# NeoKey_5x6_Ortho_Snap-Apart.net
KiCad netlist of a schematic drawn in EAGLE
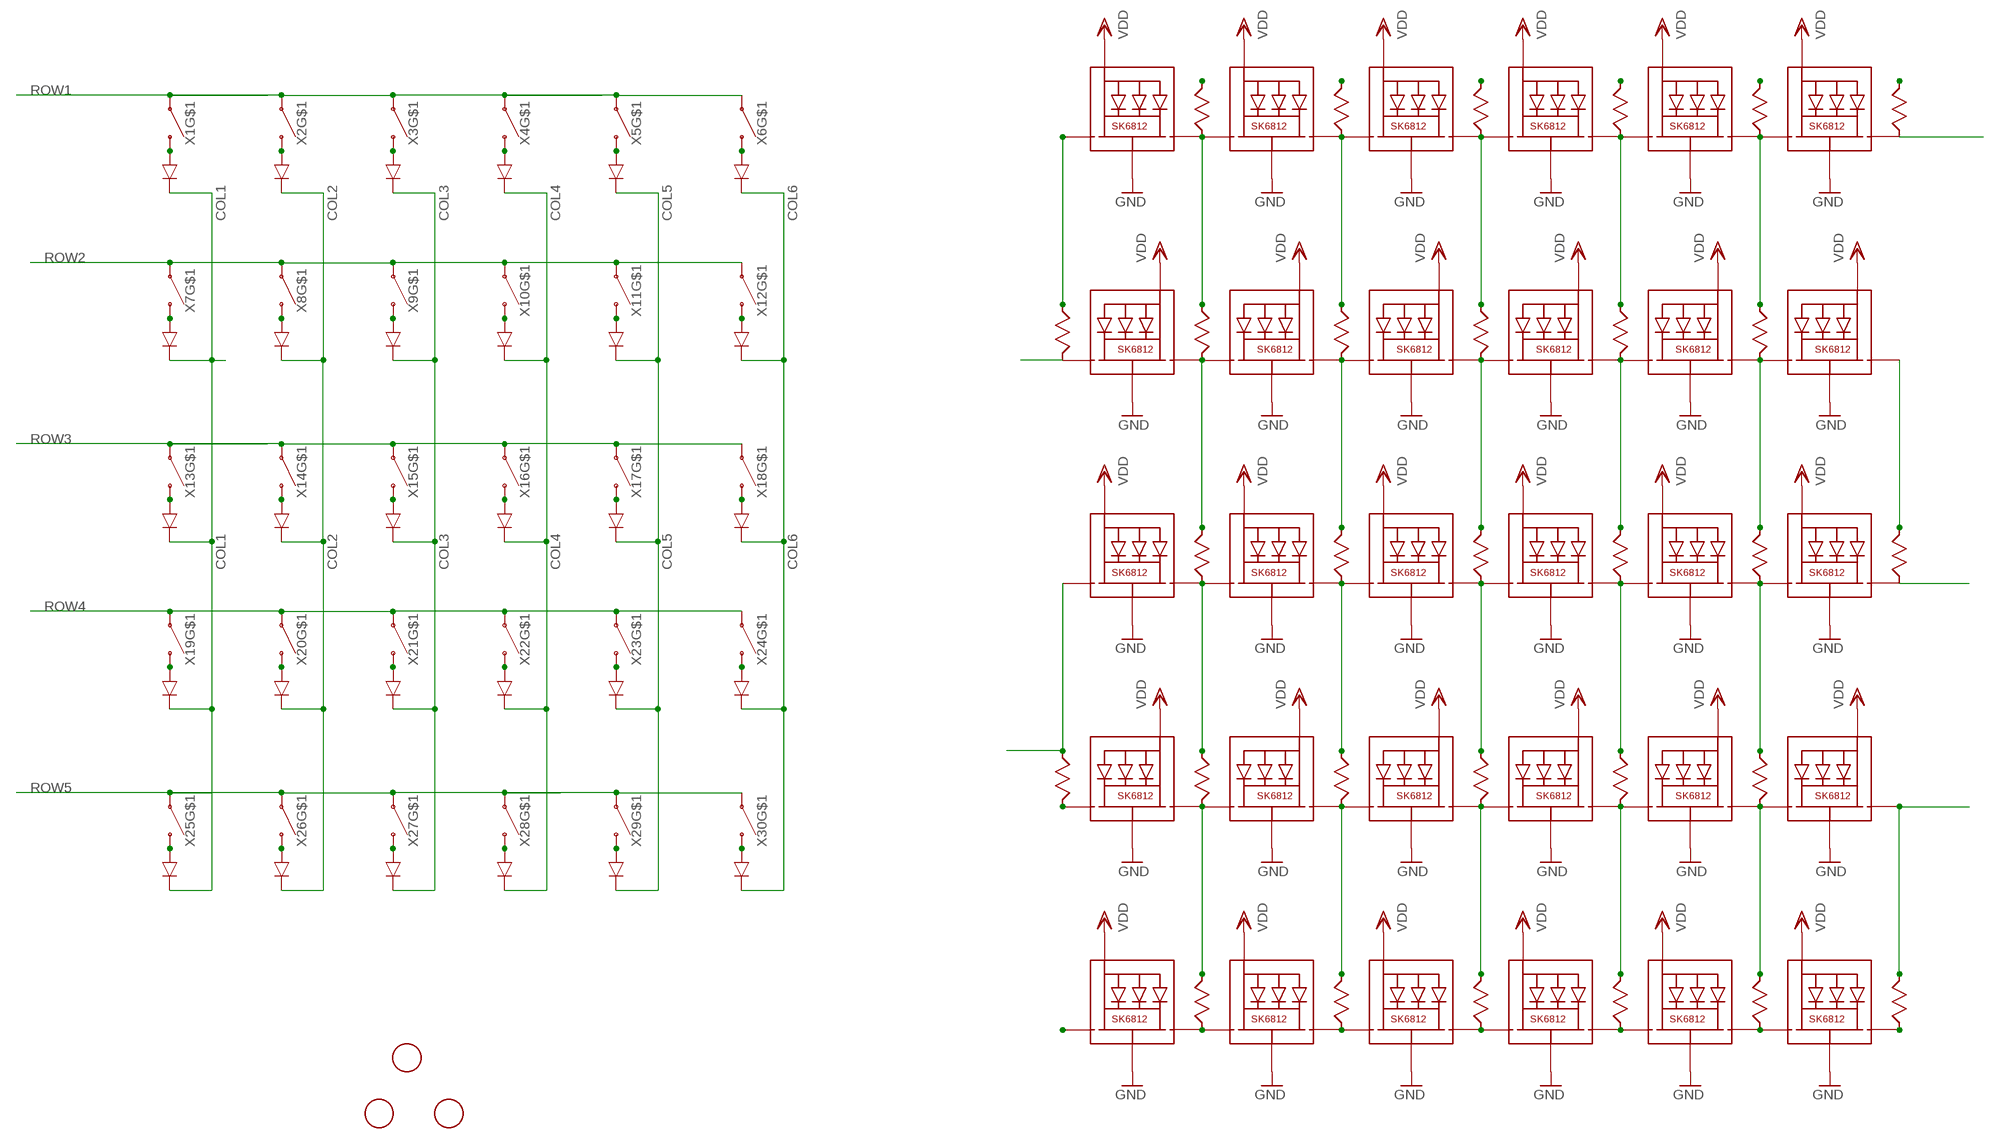
[diagram p0: schematic, sheet 1]

(export (version "E")
  (design (tool "Eeschema 10.0.6"))
  (components
    (comp (ref "U$1")
      (value "FIDUCIAL")
      (footprint "eagle-import:FIDUCIAL_1MM")
      (libsource (lib "eagle-import") (part "FIDUCIAL"))
    )
    (comp (ref "U$2")
      (value "FIDUCIAL")
      (footprint "eagle-import:FIDUCIAL_1MM")
      (libsource (lib "eagle-import") (part "FIDUCIAL"))
    )
    (comp (ref "U$3")
      (value "FIDUCIAL")
      (footprint "eagle-import:FIDUCIAL_1MM")
      (libsource (lib "eagle-import") (part "FIDUCIAL"))
    )
    (comp (ref "X1")
      (value "KAILH_SOCKET_TILE")
      (footprint "eagle-import:KAILH_SOCKET_TILE")
      (libsource (lib "eagle-import") (part "KAILH_SOCKET_TILE"))
    )
    (comp (ref "X2")
      (value "KAILH_SOCKET_TILE")
      (footprint "eagle-import:KAILH_SOCKET_TILE")
      (libsource (lib "eagle-import") (part "KAILH_SOCKET_TILE"))
    )
    (comp (ref "X3")
      (value "KAILH_SOCKET_TILE")
      (footprint "eagle-import:KAILH_SOCKET_TILE")
      (libsource (lib "eagle-import") (part "KAILH_SOCKET_TILE"))
    )
    (comp (ref "X4")
      (value "KAILH_SOCKET_TILE")
      (footprint "eagle-import:KAILH_SOCKET_TILE")
      (libsource (lib "eagle-import") (part "KAILH_SOCKET_TILE"))
    )
    (comp (ref "X5")
      (value "KAILH_SOCKET_TILE")
      (footprint "eagle-import:KAILH_SOCKET_TILE")
      (libsource (lib "eagle-import") (part "KAILH_SOCKET_TILE"))
    )
    (comp (ref "X6")
      (value "KAILH_SOCKET_TILE")
      (footprint "eagle-import:KAILH_SOCKET_TILE")
      (libsource (lib "eagle-import") (part "KAILH_SOCKET_TILE"))
    )
    (comp (ref "X7")
      (value "KAILH_SOCKET_TILE_REVERSE")
      (footprint "eagle-import:KAILH_SOCKET_TILE_REV")
      (libsource (lib "eagle-import") (part "KAILH_SOCKET_TILE_REVERSE"))
    )
    (comp (ref "X8")
      (value "KAILH_SOCKET_TILE_REVERSE")
      (footprint "eagle-import:KAILH_SOCKET_TILE_REV")
      (libsource (lib "eagle-import") (part "KAILH_SOCKET_TILE_REVERSE"))
    )
    (comp (ref "X9")
      (value "KAILH_SOCKET_TILE_REVERSE")
      (footprint "eagle-import:KAILH_SOCKET_TILE_REV")
      (libsource (lib "eagle-import") (part "KAILH_SOCKET_TILE_REVERSE"))
    )
    (comp (ref "X10")
      (value "KAILH_SOCKET_TILE_REVERSE")
      (footprint "eagle-import:KAILH_SOCKET_TILE_REV")
      (libsource (lib "eagle-import") (part "KAILH_SOCKET_TILE_REVERSE"))
    )
    (comp (ref "X11")
      (value "KAILH_SOCKET_TILE_REVERSE")
      (footprint "eagle-import:KAILH_SOCKET_TILE_REV")
      (libsource (lib "eagle-import") (part "KAILH_SOCKET_TILE_REVERSE"))
    )
    (comp (ref "X12")
      (value "KAILH_SOCKET_TILE_REVERSE")
      (footprint "eagle-import:KAILH_SOCKET_TILE_REV")
      (libsource (lib "eagle-import") (part "KAILH_SOCKET_TILE_REVERSE"))
    )
    (comp (ref "X13")
      (value "KAILH_SOCKET_TILE")
      (footprint "eagle-import:KAILH_SOCKET_TILE")
      (libsource (lib "eagle-import") (part "KAILH_SOCKET_TILE"))
    )
    (comp (ref "X14")
      (value "KAILH_SOCKET_TILE")
      (footprint "eagle-import:KAILH_SOCKET_TILE")
      (libsource (lib "eagle-import") (part "KAILH_SOCKET_TILE"))
    )
    (comp (ref "X15")
      (value "KAILH_SOCKET_TILE")
      (footprint "eagle-import:KAILH_SOCKET_TILE")
      (libsource (lib "eagle-import") (part "KAILH_SOCKET_TILE"))
    )
    (comp (ref "X16")
      (value "KAILH_SOCKET_TILE")
      (footprint "eagle-import:KAILH_SOCKET_TILE")
      (libsource (lib "eagle-import") (part "KAILH_SOCKET_TILE"))
    )
    (comp (ref "X17")
      (value "KAILH_SOCKET_TILE")
      (footprint "eagle-import:KAILH_SOCKET_TILE")
      (libsource (lib "eagle-import") (part "KAILH_SOCKET_TILE"))
    )
    (comp (ref "X18")
      (value "KAILH_SOCKET_TILE")
      (footprint "eagle-import:KAILH_SOCKET_TILE")
      (libsource (lib "eagle-import") (part "KAILH_SOCKET_TILE"))
    )
    (comp (ref "X19")
      (value "KAILH_SOCKET_TILE_REVERSE")
      (footprint "eagle-import:KAILH_SOCKET_TILE_REV")
      (libsource (lib "eagle-import") (part "KAILH_SOCKET_TILE_REVERSE"))
    )
    (comp (ref "X20")
      (value "KAILH_SOCKET_TILE_REVERSE")
      (footprint "eagle-import:KAILH_SOCKET_TILE_REV")
      (libsource (lib "eagle-import") (part "KAILH_SOCKET_TILE_REVERSE"))
    )
    (comp (ref "X21")
      (value "KAILH_SOCKET_TILE_REVERSE")
      (footprint "eagle-import:KAILH_SOCKET_TILE_REV")
      (libsource (lib "eagle-import") (part "KAILH_SOCKET_TILE_REVERSE"))
    )
    (comp (ref "X22")
      (value "KAILH_SOCKET_TILE_REVERSE")
      (footprint "eagle-import:KAILH_SOCKET_TILE_REV")
      (libsource (lib "eagle-import") (part "KAILH_SOCKET_TILE_REVERSE"))
    )
    (comp (ref "X23")
      (value "KAILH_SOCKET_TILE_REVERSE")
      (footprint "eagle-import:KAILH_SOCKET_TILE_REV")
      (libsource (lib "eagle-import") (part "KAILH_SOCKET_TILE_REVERSE"))
    )
    (comp (ref "X24")
      (value "KAILH_SOCKET_TILE_REVERSE")
      (footprint "eagle-import:KAILH_SOCKET_TILE_REV")
      (libsource (lib "eagle-import") (part "KAILH_SOCKET_TILE_REVERSE"))
    )
    (comp (ref "X25")
      (value "KAILH_SOCKET_TILE")
      (footprint "eagle-import:KAILH_SOCKET_TILE")
      (libsource (lib "eagle-import") (part "KAILH_SOCKET_TILE"))
    )
    (comp (ref "X26")
      (value "KAILH_SOCKET_TILE")
      (footprint "eagle-import:KAILH_SOCKET_TILE")
      (libsource (lib "eagle-import") (part "KAILH_SOCKET_TILE"))
    )
    (comp (ref "X27")
      (value "KAILH_SOCKET_TILE")
      (footprint "eagle-import:KAILH_SOCKET_TILE")
      (libsource (lib "eagle-import") (part "KAILH_SOCKET_TILE"))
    )
    (comp (ref "X28")
      (value "KAILH_SOCKET_TILE")
      (footprint "eagle-import:KAILH_SOCKET_TILE")
      (libsource (lib "eagle-import") (part "KAILH_SOCKET_TILE"))
    )
    (comp (ref "X29")
      (value "KAILH_SOCKET_TILE")
      (footprint "eagle-import:KAILH_SOCKET_TILE")
      (libsource (lib "eagle-import") (part "KAILH_SOCKET_TILE"))
    )
    (comp (ref "X30")
      (value "KAILH_SOCKET_TILE")
      (footprint "eagle-import:KAILH_SOCKET_TILE")
      (libsource (lib "eagle-import") (part "KAILH_SOCKET_TILE"))
    )
  )
  (nets
    (net (code "1") (name "/COL1") (class "Default")
      (node (ref "X1") (pin "C") (pinfunction "SW_C_C") (pintype "bidirectional"))
      (node (ref "X1") (pin "C1") (pinfunction "SW_C_C1") (pintype "bidirectional"))
      (node (ref "X1") (pin "C2") (pinfunction "SW_C_C2") (pintype "bidirectional"))
      (node (ref "X13") (pin "C") (pinfunction "SW_C_C") (pintype "bidirectional"))
      (node (ref "X13") (pin "C1") (pinfunction "SW_C_C1") (pintype "bidirectional"))
      (node (ref "X13") (pin "C2") (pinfunction "SW_C_C2") (pintype "bidirectional"))
      (node (ref "X19") (pin "C") (pinfunction "SW_C_C") (pintype "bidirectional"))
      (node (ref "X19") (pin "C1") (pinfunction "SW_C_C1") (pintype "bidirectional"))
      (node (ref "X19") (pin "C2") (pinfunction "SW_C_C2") (pintype "bidirectional"))
      (node (ref "X25") (pin "C") (pinfunction "SW_C_C") (pintype "bidirectional"))
      (node (ref "X25") (pin "C1") (pinfunction "SW_C_C1") (pintype "bidirectional"))
      (node (ref "X25") (pin "C2") (pinfunction "SW_C_C2") (pintype "bidirectional"))
      (node (ref "X7") (pin "C") (pinfunction "SW_C_C") (pintype "bidirectional"))
      (node (ref "X7") (pin "C1") (pinfunction "SW_C_C1") (pintype "bidirectional"))
      (node (ref "X7") (pin "C2") (pinfunction "SW_C_C2") (pintype "bidirectional"))
    )
    (net (code "2") (name "/COL2") (class "Default")
      (node (ref "X14") (pin "C") (pinfunction "SW_C_C") (pintype "bidirectional"))
      (node (ref "X14") (pin "C1") (pinfunction "SW_C_C1") (pintype "bidirectional"))
      (node (ref "X14") (pin "C2") (pinfunction "SW_C_C2") (pintype "bidirectional"))
      (node (ref "X2") (pin "C") (pinfunction "SW_C_C") (pintype "bidirectional"))
      (node (ref "X2") (pin "C1") (pinfunction "SW_C_C1") (pintype "bidirectional"))
      (node (ref "X2") (pin "C2") (pinfunction "SW_C_C2") (pintype "bidirectional"))
      (node (ref "X20") (pin "C") (pinfunction "SW_C_C") (pintype "bidirectional"))
      (node (ref "X20") (pin "C1") (pinfunction "SW_C_C1") (pintype "bidirectional"))
      (node (ref "X20") (pin "C2") (pinfunction "SW_C_C2") (pintype "bidirectional"))
      (node (ref "X26") (pin "C") (pinfunction "SW_C_C") (pintype "bidirectional"))
      (node (ref "X26") (pin "C1") (pinfunction "SW_C_C1") (pintype "bidirectional"))
      (node (ref "X26") (pin "C2") (pinfunction "SW_C_C2") (pintype "bidirectional"))
      (node (ref "X8") (pin "C") (pinfunction "SW_C_C") (pintype "bidirectional"))
      (node (ref "X8") (pin "C1") (pinfunction "SW_C_C1") (pintype "bidirectional"))
      (node (ref "X8") (pin "C2") (pinfunction "SW_C_C2") (pintype "bidirectional"))
    )
    (net (code "3") (name "/COL3") (class "Default")
      (node (ref "X15") (pin "C") (pinfunction "SW_C_C") (pintype "bidirectional"))
      (node (ref "X15") (pin "C1") (pinfunction "SW_C_C1") (pintype "bidirectional"))
      (node (ref "X15") (pin "C2") (pinfunction "SW_C_C2") (pintype "bidirectional"))
      (node (ref "X21") (pin "C") (pinfunction "SW_C_C") (pintype "bidirectional"))
      (node (ref "X21") (pin "C1") (pinfunction "SW_C_C1") (pintype "bidirectional"))
      (node (ref "X21") (pin "C2") (pinfunction "SW_C_C2") (pintype "bidirectional"))
      (node (ref "X27") (pin "C") (pinfunction "SW_C_C") (pintype "bidirectional"))
      (node (ref "X27") (pin "C1") (pinfunction "SW_C_C1") (pintype "bidirectional"))
      (node (ref "X27") (pin "C2") (pinfunction "SW_C_C2") (pintype "bidirectional"))
      (node (ref "X3") (pin "C") (pinfunction "SW_C_C") (pintype "bidirectional"))
      (node (ref "X3") (pin "C1") (pinfunction "SW_C_C1") (pintype "bidirectional"))
      (node (ref "X3") (pin "C2") (pinfunction "SW_C_C2") (pintype "bidirectional"))
      (node (ref "X9") (pin "C") (pinfunction "SW_C_C") (pintype "bidirectional"))
      (node (ref "X9") (pin "C1") (pinfunction "SW_C_C1") (pintype "bidirectional"))
      (node (ref "X9") (pin "C2") (pinfunction "SW_C_C2") (pintype "bidirectional"))
    )
    (net (code "4") (name "/COL4") (class "Default")
      (node (ref "X10") (pin "C") (pinfunction "SW_C_C") (pintype "bidirectional"))
      (node (ref "X10") (pin "C1") (pinfunction "SW_C_C1") (pintype "bidirectional"))
      (node (ref "X10") (pin "C2") (pinfunction "SW_C_C2") (pintype "bidirectional"))
      (node (ref "X16") (pin "C") (pinfunction "SW_C_C") (pintype "bidirectional"))
      (node (ref "X16") (pin "C1") (pinfunction "SW_C_C1") (pintype "bidirectional"))
      (node (ref "X16") (pin "C2") (pinfunction "SW_C_C2") (pintype "bidirectional"))
      (node (ref "X22") (pin "C") (pinfunction "SW_C_C") (pintype "bidirectional"))
      (node (ref "X22") (pin "C1") (pinfunction "SW_C_C1") (pintype "bidirectional"))
      (node (ref "X22") (pin "C2") (pinfunction "SW_C_C2") (pintype "bidirectional"))
      (node (ref "X28") (pin "C") (pinfunction "SW_C_C") (pintype "bidirectional"))
      (node (ref "X28") (pin "C1") (pinfunction "SW_C_C1") (pintype "bidirectional"))
      (node (ref "X28") (pin "C2") (pinfunction "SW_C_C2") (pintype "bidirectional"))
      (node (ref "X4") (pin "C") (pinfunction "SW_C_C") (pintype "bidirectional"))
      (node (ref "X4") (pin "C1") (pinfunction "SW_C_C1") (pintype "bidirectional"))
      (node (ref "X4") (pin "C2") (pinfunction "SW_C_C2") (pintype "bidirectional"))
    )
    (net (code "5") (name "/COL5") (class "Default")
      (node (ref "X11") (pin "C") (pinfunction "SW_C_C") (pintype "bidirectional"))
      (node (ref "X11") (pin "C1") (pinfunction "SW_C_C1") (pintype "bidirectional"))
      (node (ref "X11") (pin "C2") (pinfunction "SW_C_C2") (pintype "bidirectional"))
      (node (ref "X17") (pin "C") (pinfunction "SW_C_C") (pintype "bidirectional"))
      (node (ref "X17") (pin "C1") (pinfunction "SW_C_C1") (pintype "bidirectional"))
      (node (ref "X17") (pin "C2") (pinfunction "SW_C_C2") (pintype "bidirectional"))
      (node (ref "X23") (pin "C") (pinfunction "SW_C_C") (pintype "bidirectional"))
      (node (ref "X23") (pin "C1") (pinfunction "SW_C_C1") (pintype "bidirectional"))
      (node (ref "X23") (pin "C2") (pinfunction "SW_C_C2") (pintype "bidirectional"))
      (node (ref "X29") (pin "C") (pinfunction "SW_C_C") (pintype "bidirectional"))
      (node (ref "X29") (pin "C1") (pinfunction "SW_C_C1") (pintype "bidirectional"))
      (node (ref "X29") (pin "C2") (pinfunction "SW_C_C2") (pintype "bidirectional"))
      (node (ref "X5") (pin "C") (pinfunction "SW_C_C") (pintype "bidirectional"))
      (node (ref "X5") (pin "C1") (pinfunction "SW_C_C1") (pintype "bidirectional"))
      (node (ref "X5") (pin "C2") (pinfunction "SW_C_C2") (pintype "bidirectional"))
    )
    (net (code "6") (name "/COL6") (class "Default")
      (node (ref "X12") (pin "C") (pinfunction "SW_C_C") (pintype "bidirectional"))
      (node (ref "X12") (pin "C1") (pinfunction "SW_C_C1") (pintype "bidirectional"))
      (node (ref "X12") (pin "C2") (pinfunction "SW_C_C2") (pintype "bidirectional"))
      (node (ref "X18") (pin "C") (pinfunction "SW_C_C") (pintype "bidirectional"))
      (node (ref "X18") (pin "C1") (pinfunction "SW_C_C1") (pintype "bidirectional"))
      (node (ref "X18") (pin "C2") (pinfunction "SW_C_C2") (pintype "bidirectional"))
      (node (ref "X24") (pin "C") (pinfunction "SW_C_C") (pintype "bidirectional"))
      (node (ref "X24") (pin "C1") (pinfunction "SW_C_C1") (pintype "bidirectional"))
      (node (ref "X24") (pin "C2") (pinfunction "SW_C_C2") (pintype "bidirectional"))
      (node (ref "X30") (pin "C") (pinfunction "SW_C_C") (pintype "bidirectional"))
      (node (ref "X30") (pin "C1") (pinfunction "SW_C_C1") (pintype "bidirectional"))
      (node (ref "X30") (pin "C2") (pinfunction "SW_C_C2") (pintype "bidirectional"))
      (node (ref "X6") (pin "C") (pinfunction "SW_C_C") (pintype "bidirectional"))
      (node (ref "X6") (pin "C1") (pinfunction "SW_C_C1") (pintype "bidirectional"))
      (node (ref "X6") (pin "C2") (pinfunction "SW_C_C2") (pintype "bidirectional"))
    )
    (net (code "7") (name "/ROW1") (class "Default")
      (node (ref "X1") (pin "A") (pinfunction "SW_A_A") (pintype "bidirectional"))
      (node (ref "X1") (pin "A1") (pinfunction "SW_A_A1") (pintype "bidirectional"))
      (node (ref "X1") (pin "A2") (pinfunction "SW_A_A2") (pintype "bidirectional"))
      (node (ref "X2") (pin "A") (pinfunction "SW_A_A") (pintype "bidirectional"))
      (node (ref "X2") (pin "A1") (pinfunction "SW_A_A1") (pintype "bidirectional"))
      (node (ref "X2") (pin "A2") (pinfunction "SW_A_A2") (pintype "bidirectional"))
      (node (ref "X3") (pin "A") (pinfunction "SW_A_A") (pintype "bidirectional"))
      (node (ref "X3") (pin "A1") (pinfunction "SW_A_A1") (pintype "bidirectional"))
      (node (ref "X3") (pin "A2") (pinfunction "SW_A_A2") (pintype "bidirectional"))
      (node (ref "X4") (pin "A") (pinfunction "SW_A_A") (pintype "bidirectional"))
      (node (ref "X4") (pin "A1") (pinfunction "SW_A_A1") (pintype "bidirectional"))
      (node (ref "X4") (pin "A2") (pinfunction "SW_A_A2") (pintype "bidirectional"))
      (node (ref "X5") (pin "A") (pinfunction "SW_A_A") (pintype "bidirectional"))
      (node (ref "X5") (pin "A1") (pinfunction "SW_A_A1") (pintype "bidirectional"))
      (node (ref "X5") (pin "A2") (pinfunction "SW_A_A2") (pintype "bidirectional"))
      (node (ref "X6") (pin "A") (pinfunction "SW_A_A") (pintype "bidirectional"))
      (node (ref "X6") (pin "A1") (pinfunction "SW_A_A1") (pintype "bidirectional"))
      (node (ref "X6") (pin "A2") (pinfunction "SW_A_A2") (pintype "bidirectional"))
    )
    (net (code "8") (name "/ROW2") (class "Default")
      (node (ref "X10") (pin "A") (pinfunction "SW_A_A") (pintype "bidirectional"))
      (node (ref "X10") (pin "A1") (pinfunction "SW_A_A1") (pintype "bidirectional"))
      (node (ref "X10") (pin "A2") (pinfunction "SW_A_A2") (pintype "bidirectional"))
      (node (ref "X11") (pin "A") (pinfunction "SW_A_A") (pintype "bidirectional"))
      (node (ref "X11") (pin "A1") (pinfunction "SW_A_A1") (pintype "bidirectional"))
      (node (ref "X11") (pin "A2") (pinfunction "SW_A_A2") (pintype "bidirectional"))
      (node (ref "X12") (pin "A") (pinfunction "SW_A_A") (pintype "bidirectional"))
      (node (ref "X12") (pin "A1") (pinfunction "SW_A_A1") (pintype "bidirectional"))
      (node (ref "X12") (pin "A2") (pinfunction "SW_A_A2") (pintype "bidirectional"))
      (node (ref "X7") (pin "A") (pinfunction "SW_A_A") (pintype "bidirectional"))
      (node (ref "X7") (pin "A1") (pinfunction "SW_A_A1") (pintype "bidirectional"))
      (node (ref "X7") (pin "A2") (pinfunction "SW_A_A2") (pintype "bidirectional"))
      (node (ref "X8") (pin "A") (pinfunction "SW_A_A") (pintype "bidirectional"))
      (node (ref "X8") (pin "A1") (pinfunction "SW_A_A1") (pintype "bidirectional"))
      (node (ref "X8") (pin "A2") (pinfunction "SW_A_A2") (pintype "bidirectional"))
      (node (ref "X9") (pin "A") (pinfunction "SW_A_A") (pintype "bidirectional"))
      (node (ref "X9") (pin "A1") (pinfunction "SW_A_A1") (pintype "bidirectional"))
      (node (ref "X9") (pin "A2") (pinfunction "SW_A_A2") (pintype "bidirectional"))
    )
    (net (code "9") (name "/ROW3") (class "Default")
      (node (ref "X13") (pin "A") (pinfunction "SW_A_A") (pintype "bidirectional"))
      (node (ref "X13") (pin "A1") (pinfunction "SW_A_A1") (pintype "bidirectional"))
      (node (ref "X13") (pin "A2") (pinfunction "SW_A_A2") (pintype "bidirectional"))
      (node (ref "X14") (pin "A") (pinfunction "SW_A_A") (pintype "bidirectional"))
      (node (ref "X14") (pin "A1") (pinfunction "SW_A_A1") (pintype "bidirectional"))
      (node (ref "X14") (pin "A2") (pinfunction "SW_A_A2") (pintype "bidirectional"))
      (node (ref "X15") (pin "A") (pinfunction "SW_A_A") (pintype "bidirectional"))
      (node (ref "X15") (pin "A1") (pinfunction "SW_A_A1") (pintype "bidirectional"))
      (node (ref "X15") (pin "A2") (pinfunction "SW_A_A2") (pintype "bidirectional"))
      (node (ref "X16") (pin "A") (pinfunction "SW_A_A") (pintype "bidirectional"))
      (node (ref "X16") (pin "A1") (pinfunction "SW_A_A1") (pintype "bidirectional"))
      (node (ref "X16") (pin "A2") (pinfunction "SW_A_A2") (pintype "bidirectional"))
      (node (ref "X17") (pin "A") (pinfunction "SW_A_A") (pintype "bidirectional"))
      (node (ref "X17") (pin "A1") (pinfunction "SW_A_A1") (pintype "bidirectional"))
      (node (ref "X17") (pin "A2") (pinfunction "SW_A_A2") (pintype "bidirectional"))
      (node (ref "X18") (pin "A") (pinfunction "SW_A_A") (pintype "bidirectional"))
      (node (ref "X18") (pin "A1") (pinfunction "SW_A_A1") (pintype "bidirectional"))
      (node (ref "X18") (pin "A2") (pinfunction "SW_A_A2") (pintype "bidirectional"))
    )
    (net (code "10") (name "/ROW4") (class "Default")
      (node (ref "X19") (pin "A") (pinfunction "SW_A_A") (pintype "bidirectional"))
      (node (ref "X19") (pin "A1") (pinfunction "SW_A_A1") (pintype "bidirectional"))
      (node (ref "X19") (pin "A2") (pinfunction "SW_A_A2") (pintype "bidirectional"))
      (node (ref "X20") (pin "A") (pinfunction "SW_A_A") (pintype "bidirectional"))
      (node (ref "X20") (pin "A1") (pinfunction "SW_A_A1") (pintype "bidirectional"))
      (node (ref "X20") (pin "A2") (pinfunction "SW_A_A2") (pintype "bidirectional"))
      (node (ref "X21") (pin "A") (pinfunction "SW_A_A") (pintype "bidirectional"))
      (node (ref "X21") (pin "A1") (pinfunction "SW_A_A1") (pintype "bidirectional"))
      (node (ref "X21") (pin "A2") (pinfunction "SW_A_A2") (pintype "bidirectional"))
      (node (ref "X22") (pin "A") (pinfunction "SW_A_A") (pintype "bidirectional"))
      (node (ref "X22") (pin "A1") (pinfunction "SW_A_A1") (pintype "bidirectional"))
      (node (ref "X22") (pin "A2") (pinfunction "SW_A_A2") (pintype "bidirectional"))
      (node (ref "X23") (pin "A") (pinfunction "SW_A_A") (pintype "bidirectional"))
      (node (ref "X23") (pin "A1") (pinfunction "SW_A_A1") (pintype "bidirectional"))
      (node (ref "X23") (pin "A2") (pinfunction "SW_A_A2") (pintype "bidirectional"))
      (node (ref "X24") (pin "A") (pinfunction "SW_A_A") (pintype "bidirectional"))
      (node (ref "X24") (pin "A1") (pinfunction "SW_A_A1") (pintype "bidirectional"))
      (node (ref "X24") (pin "A2") (pinfunction "SW_A_A2") (pintype "bidirectional"))
    )
    (net (code "11") (name "/ROW5") (class "Default")
      (node (ref "X25") (pin "A") (pinfunction "SW_A_A") (pintype "bidirectional"))
      (node (ref "X25") (pin "A1") (pinfunction "SW_A_A1") (pintype "bidirectional"))
      (node (ref "X25") (pin "A2") (pinfunction "SW_A_A2") (pintype "bidirectional"))
      (node (ref "X26") (pin "A") (pinfunction "SW_A_A") (pintype "bidirectional"))
      (node (ref "X26") (pin "A1") (pinfunction "SW_A_A1") (pintype "bidirectional"))
      (node (ref "X26") (pin "A2") (pinfunction "SW_A_A2") (pintype "bidirectional"))
      (node (ref "X27") (pin "A") (pinfunction "SW_A_A") (pintype "bidirectional"))
      (node (ref "X27") (pin "A1") (pinfunction "SW_A_A1") (pintype "bidirectional"))
      (node (ref "X27") (pin "A2") (pinfunction "SW_A_A2") (pintype "bidirectional"))
      (node (ref "X28") (pin "A") (pinfunction "SW_A_A") (pintype "bidirectional"))
      (node (ref "X28") (pin "A1") (pinfunction "SW_A_A1") (pintype "bidirectional"))
      (node (ref "X28") (pin "A2") (pinfunction "SW_A_A2") (pintype "bidirectional"))
      (node (ref "X29") (pin "A") (pinfunction "SW_A_A") (pintype "bidirectional"))
      (node (ref "X29") (pin "A1") (pinfunction "SW_A_A1") (pintype "bidirectional"))
      (node (ref "X29") (pin "A2") (pinfunction "SW_A_A2") (pintype "bidirectional"))
      (node (ref "X30") (pin "A") (pinfunction "SW_A_A") (pintype "bidirectional"))
      (node (ref "X30") (pin "A1") (pinfunction "SW_A_A1") (pintype "bidirectional"))
      (node (ref "X30") (pin "A2") (pinfunction "SW_A_A2") (pintype "bidirectional"))
    )
    (net (code "12") (name "GND") (class "Default")
      (node (ref "X1") (pin "3-GND") (pinfunction "GND_3-GND") (pintype "power_in"))
      (node (ref "X1") (pin "C-") (pinfunction "GND_C-") (pintype "power_in"))
      (node (ref "X1") (pin "GND1") (pinfunction "GND_GND1") (pintype "power_in"))
      (node (ref "X1") (pin "GND2") (pinfunction "GND_GND2") (pintype "power_in"))
      (node (ref "X10") (pin "3-GND") (pinfunction "GND_3-GND") (pintype "power_in"))
      (node (ref "X10") (pin "C-") (pinfunction "GND_C-") (pintype "power_in"))
      (node (ref "X10") (pin "GND1") (pinfunction "GND_GND1") (pintype "power_in"))
      (node (ref "X10") (pin "GND2") (pinfunction "GND_GND2") (pintype "power_in"))
      (node (ref "X11") (pin "3-GND") (pinfunction "GND_3-GND") (pintype "power_in"))
      (node (ref "X11") (pin "C-") (pinfunction "GND_C-") (pintype "power_in"))
      (node (ref "X11") (pin "GND1") (pinfunction "GND_GND1") (pintype "power_in"))
      (node (ref "X11") (pin "GND2") (pinfunction "GND_GND2") (pintype "power_in"))
      (node (ref "X12") (pin "3-GND") (pinfunction "GND_3-GND") (pintype "power_in"))
      (node (ref "X12") (pin "C-") (pinfunction "GND_C-") (pintype "power_in"))
      (node (ref "X12") (pin "GND1") (pinfunction "GND_GND1") (pintype "power_in"))
      (node (ref "X12") (pin "GND2") (pinfunction "GND_GND2") (pintype "power_in"))
      (node (ref "X13") (pin "3-GND") (pinfunction "GND_3-GND") (pintype "power_in"))
      (node (ref "X13") (pin "C-") (pinfunction "GND_C-") (pintype "power_in"))
      (node (ref "X13") (pin "GND1") (pinfunction "GND_GND1") (pintype "power_in"))
      (node (ref "X13") (pin "GND2") (pinfunction "GND_GND2") (pintype "power_in"))
      (node (ref "X14") (pin "3-GND") (pinfunction "GND_3-GND") (pintype "power_in"))
      (node (ref "X14") (pin "C-") (pinfunction "GND_C-") (pintype "power_in"))
      (node (ref "X14") (pin "GND1") (pinfunction "GND_GND1") (pintype "power_in"))
      (node (ref "X14") (pin "GND2") (pinfunction "GND_GND2") (pintype "power_in"))
      (node (ref "X15") (pin "3-GND") (pinfunction "GND_3-GND") (pintype "power_in"))
      (node (ref "X15") (pin "C-") (pinfunction "GND_C-") (pintype "power_in"))
      (node (ref "X15") (pin "GND1") (pinfunction "GND_GND1") (pintype "power_in"))
      (node (ref "X15") (pin "GND2") (pinfunction "GND_GND2") (pintype "power_in"))
      (node (ref "X16") (pin "3-GND") (pinfunction "GND_3-GND") (pintype "power_in"))
      (node (ref "X16") (pin "C-") (pinfunction "GND_C-") (pintype "power_in"))
      (node (ref "X16") (pin "GND1") (pinfunction "GND_GND1") (pintype "power_in"))
      (node (ref "X16") (pin "GND2") (pinfunction "GND_GND2") (pintype "power_in"))
      (node (ref "X17") (pin "3-GND") (pinfunction "GND_3-GND") (pintype "power_in"))
      (node (ref "X17") (pin "C-") (pinfunction "GND_C-") (pintype "power_in"))
      (node (ref "X17") (pin "GND1") (pinfunction "GND_GND1") (pintype "power_in"))
      (node (ref "X17") (pin "GND2") (pinfunction "GND_GND2") (pintype "power_in"))
      (node (ref "X18") (pin "3-GND") (pinfunction "GND_3-GND") (pintype "power_in"))
      (node (ref "X18") (pin "C-") (pinfunction "GND_C-") (pintype "power_in"))
      (node (ref "X18") (pin "GND1") (pinfunction "GND_GND1") (pintype "power_in"))
      (node (ref "X18") (pin "GND2") (pinfunction "GND_GND2") (pintype "power_in"))
      (node (ref "X19") (pin "3-GND") (pinfunction "GND_3-GND") (pintype "power_in"))
      (node (ref "X19") (pin "C-") (pinfunction "GND_C-") (pintype "power_in"))
      (node (ref "X19") (pin "GND1") (pinfunction "GND_GND1") (pintype "power_in"))
      (node (ref "X19") (pin "GND2") (pinfunction "GND_GND2") (pintype "power_in"))
      (node (ref "X2") (pin "3-GND") (pinfunction "GND_3-GND") (pintype "power_in"))
      (node (ref "X2") (pin "C-") (pinfunction "GND_C-") (pintype "power_in"))
      (node (ref "X2") (pin "GND1") (pinfunction "GND_GND1") (pintype "power_in"))
      (node (ref "X2") (pin "GND2") (pinfunction "GND_GND2") (pintype "power_in"))
      (node (ref "X20") (pin "3-GND") (pinfunction "GND_3-GND") (pintype "power_in"))
      (node (ref "X20") (pin "C-") (pinfunction "GND_C-") (pintype "power_in"))
      (node (ref "X20") (pin "GND1") (pinfunction "GND_GND1") (pintype "power_in"))
      (node (ref "X20") (pin "GND2") (pinfunction "GND_GND2") (pintype "power_in"))
      (node (ref "X21") (pin "3-GND") (pinfunction "GND_3-GND") (pintype "power_in"))
      (node (ref "X21") (pin "C-") (pinfunction "GND_C-") (pintype "power_in"))
      (node (ref "X21") (pin "GND1") (pinfunction "GND_GND1") (pintype "power_in"))
      (node (ref "X21") (pin "GND2") (pinfunction "GND_GND2") (pintype "power_in"))
      (node (ref "X22") (pin "3-GND") (pinfunction "GND_3-GND") (pintype "power_in"))
      (node (ref "X22") (pin "C-") (pinfunction "GND_C-") (pintype "power_in"))
      (node (ref "X22") (pin "GND1") (pinfunction "GND_GND1") (pintype "power_in"))
      (node (ref "X22") (pin "GND2") (pinfunction "GND_GND2") (pintype "power_in"))
      (node (ref "X23") (pin "3-GND") (pinfunction "GND_3-GND") (pintype "power_in"))
      (node (ref "X23") (pin "C-") (pinfunction "GND_C-") (pintype "power_in"))
      (node (ref "X23") (pin "GND1") (pinfunction "GND_GND1") (pintype "power_in"))
      (node (ref "X23") (pin "GND2") (pinfunction "GND_GND2") (pintype "power_in"))
      (node (ref "X24") (pin "3-GND") (pinfunction "GND_3-GND") (pintype "power_in"))
      (node (ref "X24") (pin "C-") (pinfunction "GND_C-") (pintype "power_in"))
      (node (ref "X24") (pin "GND1") (pinfunction "GND_GND1") (pintype "power_in"))
      (node (ref "X24") (pin "GND2") (pinfunction "GND_GND2") (pintype "power_in"))
      (node (ref "X25") (pin "3-GND") (pinfunction "GND_3-GND") (pintype "power_in"))
      (node (ref "X25") (pin "C-") (pinfunction "GND_C-") (pintype "power_in"))
      (node (ref "X25") (pin "GND1") (pinfunction "GND_GND1") (pintype "power_in"))
      (node (ref "X25") (pin "GND2") (pinfunction "GND_GND2") (pintype "power_in"))
      (node (ref "X26") (pin "3-GND") (pinfunction "GND_3-GND") (pintype "power_in"))
      (node (ref "X26") (pin "C-") (pinfunction "GND_C-") (pintype "power_in"))
      (node (ref "X26") (pin "GND1") (pinfunction "GND_GND1") (pintype "power_in"))
      (node (ref "X26") (pin "GND2") (pinfunction "GND_GND2") (pintype "power_in"))
      (node (ref "X27") (pin "3-GND") (pinfunction "GND_3-GND") (pintype "power_in"))
      (node (ref "X27") (pin "C-") (pinfunction "GND_C-") (pintype "power_in"))
      (node (ref "X27") (pin "GND1") (pinfunction "GND_GND1") (pintype "power_in"))
      (node (ref "X27") (pin "GND2") (pinfunction "GND_GND2") (pintype "power_in"))
      (node (ref "X28") (pin "3-GND") (pinfunction "GND_3-GND") (pintype "power_in"))
      (node (ref "X28") (pin "C-") (pinfunction "GND_C-") (pintype "power_in"))
      (node (ref "X28") (pin "GND1") (pinfunction "GND_GND1") (pintype "power_in"))
      (node (ref "X28") (pin "GND2") (pinfunction "GND_GND2") (pintype "power_in"))
      (node (ref "X29") (pin "3-GND") (pinfunction "GND_3-GND") (pintype "power_in"))
      (node (ref "X29") (pin "C-") (pinfunction "GND_C-") (pintype "power_in"))
      (node (ref "X29") (pin "GND1") (pinfunction "GND_GND1") (pintype "power_in"))
      (node (ref "X29") (pin "GND2") (pinfunction "GND_GND2") (pintype "power_in"))
      (node (ref "X3") (pin "3-GND") (pinfunction "GND_3-GND") (pintype "power_in"))
      (node (ref "X3") (pin "C-") (pinfunction "GND_C-") (pintype "power_in"))
      (node (ref "X3") (pin "GND1") (pinfunction "GND_GND1") (pintype "power_in"))
      (node (ref "X3") (pin "GND2") (pinfunction "GND_GND2") (pintype "power_in"))
      (node (ref "X30") (pin "3-GND") (pinfunction "GND_3-GND") (pintype "power_in"))
      (node (ref "X30") (pin "C-") (pinfunction "GND_C-") (pintype "power_in"))
      (node (ref "X30") (pin "GND1") (pinfunction "GND_GND1") (pintype "power_in"))
      (node (ref "X30") (pin "GND2") (pinfunction "GND_GND2") (pintype "power_in"))
      (node (ref "X4") (pin "3-GND") (pinfunction "GND_3-GND") (pintype "power_in"))
      (node (ref "X4") (pin "C-") (pinfunction "GND_C-") (pintype "power_in"))
      (node (ref "X4") (pin "GND1") (pinfunction "GND_GND1") (pintype "power_in"))
      (node (ref "X4") (pin "GND2") (pinfunction "GND_GND2") (pintype "power_in"))
      (node (ref "X5") (pin "3-GND") (pinfunction "GND_3-GND") (pintype "power_in"))
      (node (ref "X5") (pin "C-") (pinfunction "GND_C-") (pintype "power_in"))
      (node (ref "X5") (pin "GND1") (pinfunction "GND_GND1") (pintype "power_in"))
      (node (ref "X5") (pin "GND2") (pinfunction "GND_GND2") (pintype "power_in"))
      (node (ref "X6") (pin "3-GND") (pinfunction "GND_3-GND") (pintype "power_in"))
      (node (ref "X6") (pin "C-") (pinfunction "GND_C-") (pintype "power_in"))
      (node (ref "X6") (pin "GND1") (pinfunction "GND_GND1") (pintype "power_in"))
      (node (ref "X6") (pin "GND2") (pinfunction "GND_GND2") (pintype "power_in"))
      (node (ref "X7") (pin "3-GND") (pinfunction "GND_3-GND") (pintype "power_in"))
      (node (ref "X7") (pin "C-") (pinfunction "GND_C-") (pintype "power_in"))
      (node (ref "X7") (pin "GND1") (pinfunction "GND_GND1") (pintype "power_in"))
      (node (ref "X7") (pin "GND2") (pinfunction "GND_GND2") (pintype "power_in"))
      (node (ref "X8") (pin "3-GND") (pinfunction "GND_3-GND") (pintype "power_in"))
      (node (ref "X8") (pin "C-") (pinfunction "GND_C-") (pintype "power_in"))
      (node (ref "X8") (pin "GND1") (pinfunction "GND_GND1") (pintype "power_in"))
      (node (ref "X8") (pin "GND2") (pinfunction "GND_GND2") (pintype "power_in"))
      (node (ref "X9") (pin "3-GND") (pinfunction "GND_3-GND") (pintype "power_in"))
      (node (ref "X9") (pin "C-") (pinfunction "GND_C-") (pintype "power_in"))
      (node (ref "X9") (pin "GND1") (pinfunction "GND_GND1") (pintype "power_in"))
      (node (ref "X9") (pin "GND2") (pinfunction "GND_GND2") (pintype "power_in"))
    )
    (net (code "13") (name "Net-(X1-PadDA)") (class "Default")
      (node (ref "X1") (pin "D+") (pinfunction "DA_D+") (pintype "bidirectional"))
      (node (ref "X1") (pin "DA") (pinfunction "DA_DA") (pintype "bidirectional"))
    )
    (net (code "14") (name "Net-(X1B-DI-Pad4-DIN)") (class "Default")
      (node (ref "X1") (pin "4-DIN") (pinfunction "DI_4-DIN") (pintype "input"))
      (node (ref "X1") (pin "DIN") (pinfunction "DI_DIN") (pintype "input"))
      (node (ref "X1") (pin "DIN1") (pinfunction "DI_DIN1") (pintype "input"))
      (node (ref "X2") (pin "2-DOUT") (pinfunction "DO_2-DOUT") (pintype "output"))
      (node (ref "X2") (pin "DOUT") (pinfunction "DO_DOUT") (pintype "output"))
      (node (ref "X2") (pin "DOUT1") (pinfunction "DO_DOUT1") (pintype "output"))
      (node (ref "X8") (pin "DIN_C") (pinfunction "DI1_DIN_C") (pintype "input"))
      (node (ref "X8") (pin "DIN_C1") (pinfunction "DI1_DIN_C1") (pintype "input"))
    )
    (net (code "15") (name "Net-(X1B-DI1-PadDIN_C)") (class "Default")
      (node (ref "X1") (pin "DIN_C") (pinfunction "DI1_DIN_C") (pintype "input"))
      (node (ref "X1") (pin "DIN_C1") (pinfunction "DI1_DIN_C1") (pintype "input"))
    )
    (net (code "16") (name "Net-(X1B-DO-Pad2-DOUT)") (class "Default")
      (node (ref "X1") (pin "2-DOUT") (pinfunction "DO_2-DOUT") (pintype "output"))
      (node (ref "X1") (pin "DOUT") (pinfunction "DO_DOUT") (pintype "output"))
      (node (ref "X1") (pin "DOUT1") (pinfunction "DO_DOUT1") (pintype "output"))
      (node (ref "X7") (pin "DIN_C") (pinfunction "DI1_DIN_C") (pintype "input"))
      (node (ref "X7") (pin "DIN_C1") (pinfunction "DI1_DIN_C1") (pintype "input"))
    )
    (net (code "17") (name "Net-(X2-PadDA)") (class "Default")
      (node (ref "X2") (pin "D+") (pinfunction "DA_D+") (pintype "bidirectional"))
      (node (ref "X2") (pin "DA") (pinfunction "DA_DA") (pintype "bidirectional"))
    )
    (net (code "18") (name "Net-(X2B-DI-Pad4-DIN)") (class "Default")
      (node (ref "X2") (pin "4-DIN") (pinfunction "DI_4-DIN") (pintype "input"))
      (node (ref "X2") (pin "DIN") (pinfunction "DI_DIN") (pintype "input"))
      (node (ref "X2") (pin "DIN1") (pinfunction "DI_DIN1") (pintype "input"))
      (node (ref "X3") (pin "2-DOUT") (pinfunction "DO_2-DOUT") (pintype "output"))
      (node (ref "X3") (pin "DOUT") (pinfunction "DO_DOUT") (pintype "output"))
      (node (ref "X3") (pin "DOUT1") (pinfunction "DO_DOUT1") (pintype "output"))
      (node (ref "X9") (pin "DIN_C") (pinfunction "DI1_DIN_C") (pintype "input"))
      (node (ref "X9") (pin "DIN_C1") (pinfunction "DI1_DIN_C1") (pintype "input"))
    )
    (net (code "19") (name "Net-(X2B-DI1-PadDIN_C)") (class "Default")
      (node (ref "X2") (pin "DIN_C") (pinfunction "DI1_DIN_C") (pintype "input"))
      (node (ref "X2") (pin "DIN_C1") (pinfunction "DI1_DIN_C1") (pintype "input"))
    )
    (net (code "20") (name "Net-(X3-PadDA)") (class "Default")
      (node (ref "X3") (pin "D+") (pinfunction "DA_D+") (pintype "bidirectional"))
      (node (ref "X3") (pin "DA") (pinfunction "DA_DA") (pintype "bidirectional"))
    )
    (net (code "21") (name "Net-(X3B-DI1-PadDIN_C)") (class "Default")
      (node (ref "X3") (pin "DIN_C") (pinfunction "DI1_DIN_C") (pintype "input"))
      (node (ref "X3") (pin "DIN_C1") (pinfunction "DI1_DIN_C1") (pintype "input"))
    )
    (net (code "22") (name "Net-(X4-PadDA)") (class "Default")
      (node (ref "X4") (pin "D+") (pinfunction "DA_D+") (pintype "bidirectional"))
      (node (ref "X4") (pin "DA") (pinfunction "DA_DA") (pintype "bidirectional"))
    )
    (net (code "23") (name "Net-(X4B-DI1-PadDIN_C)") (class "Default")
      (node (ref "X4") (pin "DIN_C") (pinfunction "DI1_DIN_C") (pintype "input"))
      (node (ref "X4") (pin "DIN_C1") (pinfunction "DI1_DIN_C1") (pintype "input"))
    )
    (net (code "24") (name "Net-(X5-PadDA)") (class "Default")
      (node (ref "X5") (pin "D+") (pinfunction "DA_D+") (pintype "bidirectional"))
      (node (ref "X5") (pin "DA") (pinfunction "DA_DA") (pintype "bidirectional"))
    )
    (net (code "25") (name "Net-(X5B-DI1-PadDIN_C)") (class "Default")
      (node (ref "X5") (pin "DIN_C") (pinfunction "DI1_DIN_C") (pintype "input"))
      (node (ref "X5") (pin "DIN_C1") (pinfunction "DI1_DIN_C1") (pintype "input"))
    )
    (net (code "26") (name "Net-(X6-PadDA)") (class "Default")
      (node (ref "X6") (pin "D+") (pinfunction "DA_D+") (pintype "bidirectional"))
      (node (ref "X6") (pin "DA") (pinfunction "DA_DA") (pintype "bidirectional"))
    )
    (net (code "27") (name "Net-(X6B-DI-Pad4-DIN)") (class "Default")
      (node (ref "X6") (pin "4-DIN") (pinfunction "DI_4-DIN") (pintype "input"))
      (node (ref "X6") (pin "DIN") (pinfunction "DI_DIN") (pintype "input"))
      (node (ref "X6") (pin "DIN1") (pinfunction "DI_DIN1") (pintype "input"))
    )
    (net (code "28") (name "Net-(X6B-DI1-PadDIN_C)") (class "Default")
      (node (ref "X6") (pin "DIN_C") (pinfunction "DI1_DIN_C") (pintype "input"))
      (node (ref "X6") (pin "DIN_C1") (pinfunction "DI1_DIN_C1") (pintype "input"))
    )
    (net (code "29") (name "Net-(X7-PadDA)") (class "Default")
      (node (ref "X7") (pin "D+") (pinfunction "DA_D+") (pintype "bidirectional"))
      (node (ref "X7") (pin "DA") (pinfunction "DA_DA") (pintype "bidirectional"))
    )
    (net (code "30") (name "Net-(X7B-DI-Pad4-DIN)") (class "Default")
      (node (ref "X7") (pin "4-DIN") (pinfunction "DI_4-DIN") (pintype "input"))
      (node (ref "X7") (pin "DIN") (pinfunction "DI_DIN") (pintype "input"))
      (node (ref "X7") (pin "DIN1") (pinfunction "DI_DIN1") (pintype "input"))
    )
    (net (code "31") (name "Net-(X8-PadDA)") (class "Default")
      (node (ref "X8") (pin "D+") (pinfunction "DA_D+") (pintype "bidirectional"))
      (node (ref "X8") (pin "DA") (pinfunction "DA_DA") (pintype "bidirectional"))
    )
    (net (code "32") (name "Net-(X9-PadDA)") (class "Default")
      (node (ref "X9") (pin "D+") (pinfunction "DA_D+") (pintype "bidirectional"))
      (node (ref "X9") (pin "DA") (pinfunction "DA_DA") (pintype "bidirectional"))
    )
    (net (code "33") (name "Net-(X10-PadDA)") (class "Default")
      (node (ref "X10") (pin "D+") (pinfunction "DA_D+") (pintype "bidirectional"))
      (node (ref "X10") (pin "DA") (pinfunction "DA_DA") (pintype "bidirectional"))
    )
    (net (code "34") (name "Net-(X10B-DI-Pad4-DIN)") (class "Default")
      (node (ref "X10") (pin "4-DIN") (pinfunction "DI_4-DIN") (pintype "input"))
      (node (ref "X10") (pin "DIN") (pinfunction "DI_DIN") (pintype "input"))
      (node (ref "X10") (pin "DIN1") (pinfunction "DI_DIN1") (pintype "input"))
      (node (ref "X15") (pin "DIN_C") (pinfunction "DI1_DIN_C") (pintype "input"))
      (node (ref "X15") (pin "DIN_C1") (pinfunction "DI1_DIN_C1") (pintype "input"))
      (node (ref "X9") (pin "2-DOUT") (pinfunction "DO_2-DOUT") (pintype "output"))
      (node (ref "X9") (pin "DOUT") (pinfunction "DO_DOUT") (pintype "output"))
      (node (ref "X9") (pin "DOUT1") (pinfunction "DO_DOUT1") (pintype "output"))
    )
    (net (code "35") (name "Net-(X10B-DI1-PadDIN_C)") (class "Default")
      (node (ref "X10") (pin "DIN_C") (pinfunction "DI1_DIN_C") (pintype "input"))
      (node (ref "X10") (pin "DIN_C1") (pinfunction "DI1_DIN_C1") (pintype "input"))
      (node (ref "X3") (pin "4-DIN") (pinfunction "DI_4-DIN") (pintype "input"))
      (node (ref "X3") (pin "DIN") (pinfunction "DI_DIN") (pintype "input"))
      (node (ref "X3") (pin "DIN1") (pinfunction "DI_DIN1") (pintype "input"))
      (node (ref "X4") (pin "2-DOUT") (pinfunction "DO_2-DOUT") (pintype "output"))
      (node (ref "X4") (pin "DOUT") (pinfunction "DO_DOUT") (pintype "output"))
      (node (ref "X4") (pin "DOUT1") (pinfunction "DO_DOUT1") (pintype "output"))
    )
    (net (code "36") (name "Net-(X10B-DO-Pad2-DOUT)") (class "Default")
      (node (ref "X10") (pin "2-DOUT") (pinfunction "DO_2-DOUT") (pintype "output"))
      (node (ref "X10") (pin "DOUT") (pinfunction "DO_DOUT") (pintype "output"))
      (node (ref "X10") (pin "DOUT1") (pinfunction "DO_DOUT1") (pintype "output"))
      (node (ref "X11") (pin "4-DIN") (pinfunction "DI_4-DIN") (pintype "input"))
      (node (ref "X11") (pin "DIN") (pinfunction "DI_DIN") (pintype "input"))
      (node (ref "X11") (pin "DIN1") (pinfunction "DI_DIN1") (pintype "input"))
      (node (ref "X16") (pin "DIN_C") (pinfunction "DI1_DIN_C") (pintype "input"))
      (node (ref "X16") (pin "DIN_C1") (pinfunction "DI1_DIN_C1") (pintype "input"))
    )
    (net (code "37") (name "Net-(X11-PadDA)") (class "Default")
      (node (ref "X11") (pin "D+") (pinfunction "DA_D+") (pintype "bidirectional"))
      (node (ref "X11") (pin "DA") (pinfunction "DA_DA") (pintype "bidirectional"))
    )
    (net (code "38") (name "Net-(X11B-DI1-PadDIN_C)") (class "Default")
      (node (ref "X11") (pin "DIN_C") (pinfunction "DI1_DIN_C") (pintype "input"))
      (node (ref "X11") (pin "DIN_C1") (pinfunction "DI1_DIN_C1") (pintype "input"))
      (node (ref "X4") (pin "4-DIN") (pinfunction "DI_4-DIN") (pintype "input"))
      (node (ref "X4") (pin "DIN") (pinfunction "DI_DIN") (pintype "input"))
      (node (ref "X4") (pin "DIN1") (pinfunction "DI_DIN1") (pintype "input"))
      (node (ref "X5") (pin "2-DOUT") (pinfunction "DO_2-DOUT") (pintype "output"))
      (node (ref "X5") (pin "DOUT") (pinfunction "DO_DOUT") (pintype "output"))
      (node (ref "X5") (pin "DOUT1") (pinfunction "DO_DOUT1") (pintype "output"))
    )
    (net (code "39") (name "Net-(X11B-DO-Pad2-DOUT)") (class "Default")
      (node (ref "X11") (pin "2-DOUT") (pinfunction "DO_2-DOUT") (pintype "output"))
      (node (ref "X11") (pin "DOUT") (pinfunction "DO_DOUT") (pintype "output"))
      (node (ref "X11") (pin "DOUT1") (pinfunction "DO_DOUT1") (pintype "output"))
      (node (ref "X12") (pin "4-DIN") (pinfunction "DI_4-DIN") (pintype "input"))
      (node (ref "X12") (pin "DIN") (pinfunction "DI_DIN") (pintype "input"))
      (node (ref "X12") (pin "DIN1") (pinfunction "DI_DIN1") (pintype "input"))
      (node (ref "X17") (pin "DIN_C") (pinfunction "DI1_DIN_C") (pintype "input"))
      (node (ref "X17") (pin "DIN_C1") (pinfunction "DI1_DIN_C1") (pintype "input"))
    )
    (net (code "40") (name "Net-(X12-PadDA)") (class "Default")
      (node (ref "X12") (pin "D+") (pinfunction "DA_D+") (pintype "bidirectional"))
      (node (ref "X12") (pin "DA") (pinfunction "DA_DA") (pintype "bidirectional"))
    )
    (net (code "41") (name "Net-(X12B-DI1-PadDIN_C)") (class "Default")
      (node (ref "X12") (pin "DIN_C") (pinfunction "DI1_DIN_C") (pintype "input"))
      (node (ref "X12") (pin "DIN_C1") (pinfunction "DI1_DIN_C1") (pintype "input"))
      (node (ref "X5") (pin "4-DIN") (pinfunction "DI_4-DIN") (pintype "input"))
      (node (ref "X5") (pin "DIN") (pinfunction "DI_DIN") (pintype "input"))
      (node (ref "X5") (pin "DIN1") (pinfunction "DI_DIN1") (pintype "input"))
      (node (ref "X6") (pin "2-DOUT") (pinfunction "DO_2-DOUT") (pintype "output"))
      (node (ref "X6") (pin "DOUT") (pinfunction "DO_DOUT") (pintype "output"))
      (node (ref "X6") (pin "DOUT1") (pinfunction "DO_DOUT1") (pintype "output"))
    )
    (net (code "42") (name "Net-(X12B-DO-Pad2-DOUT)") (class "Default")
      (node (ref "X12") (pin "2-DOUT") (pinfunction "DO_2-DOUT") (pintype "output"))
      (node (ref "X12") (pin "DOUT") (pinfunction "DO_DOUT") (pintype "output"))
      (node (ref "X12") (pin "DOUT1") (pinfunction "DO_DOUT1") (pintype "output"))
      (node (ref "X18") (pin "DIN_C") (pinfunction "DI1_DIN_C") (pintype "input"))
      (node (ref "X18") (pin "DIN_C1") (pinfunction "DI1_DIN_C1") (pintype "input"))
    )
    (net (code "43") (name "Net-(X13-PadDA)") (class "Default")
      (node (ref "X13") (pin "D+") (pinfunction "DA_D+") (pintype "bidirectional"))
      (node (ref "X13") (pin "DA") (pinfunction "DA_DA") (pintype "bidirectional"))
    )
    (net (code "44") (name "Net-(X13B-DI-Pad4-DIN)") (class "Default")
      (node (ref "X13") (pin "4-DIN") (pinfunction "DI_4-DIN") (pintype "input"))
      (node (ref "X13") (pin "DIN") (pinfunction "DI_DIN") (pintype "input"))
      (node (ref "X13") (pin "DIN1") (pinfunction "DI_DIN1") (pintype "input"))
      (node (ref "X14") (pin "2-DOUT") (pinfunction "DO_2-DOUT") (pintype "output"))
      (node (ref "X14") (pin "DOUT") (pinfunction "DO_DOUT") (pintype "output"))
      (node (ref "X14") (pin "DOUT1") (pinfunction "DO_DOUT1") (pintype "output"))
      (node (ref "X20") (pin "DIN_C") (pinfunction "DI1_DIN_C") (pintype "input"))
      (node (ref "X20") (pin "DIN_C1") (pinfunction "DI1_DIN_C1") (pintype "input"))
    )
    (net (code "45") (name "Net-(X13B-DI1-PadDIN_C)") (class "Default")
      (node (ref "X13") (pin "DIN_C") (pinfunction "DI1_DIN_C") (pintype "input"))
      (node (ref "X13") (pin "DIN_C1") (pinfunction "DI1_DIN_C1") (pintype "input"))
      (node (ref "X7") (pin "2-DOUT") (pinfunction "DO_2-DOUT") (pintype "output"))
      (node (ref "X7") (pin "DOUT") (pinfunction "DO_DOUT") (pintype "output"))
      (node (ref "X7") (pin "DOUT1") (pinfunction "DO_DOUT1") (pintype "output"))
      (node (ref "X8") (pin "4-DIN") (pinfunction "DI_4-DIN") (pintype "input"))
      (node (ref "X8") (pin "DIN") (pinfunction "DI_DIN") (pintype "input"))
      (node (ref "X8") (pin "DIN1") (pinfunction "DI_DIN1") (pintype "input"))
    )
    (net (code "46") (name "Net-(X13B-DO-Pad2-DOUT)") (class "Default")
      (node (ref "X13") (pin "2-DOUT") (pinfunction "DO_2-DOUT") (pintype "output"))
      (node (ref "X13") (pin "DOUT") (pinfunction "DO_DOUT") (pintype "output"))
      (node (ref "X13") (pin "DOUT1") (pinfunction "DO_DOUT1") (pintype "output"))
      (node (ref "X19") (pin "DIN_C") (pinfunction "DI1_DIN_C") (pintype "input"))
      (node (ref "X19") (pin "DIN_C1") (pinfunction "DI1_DIN_C1") (pintype "input"))
    )
    (net (code "47") (name "Net-(X14-PadDA)") (class "Default")
      (node (ref "X14") (pin "D+") (pinfunction "DA_D+") (pintype "bidirectional"))
      (node (ref "X14") (pin "DA") (pinfunction "DA_DA") (pintype "bidirectional"))
    )
    (net (code "48") (name "Net-(X14B-DI-Pad4-DIN)") (class "Default")
      (node (ref "X14") (pin "4-DIN") (pinfunction "DI_4-DIN") (pintype "input"))
      (node (ref "X14") (pin "DIN") (pinfunction "DI_DIN") (pintype "input"))
      (node (ref "X14") (pin "DIN1") (pinfunction "DI_DIN1") (pintype "input"))
      (node (ref "X15") (pin "2-DOUT") (pinfunction "DO_2-DOUT") (pintype "output"))
      (node (ref "X15") (pin "DOUT") (pinfunction "DO_DOUT") (pintype "output"))
      (node (ref "X15") (pin "DOUT1") (pinfunction "DO_DOUT1") (pintype "output"))
      (node (ref "X21") (pin "DIN_C") (pinfunction "DI1_DIN_C") (pintype "input"))
      (node (ref "X21") (pin "DIN_C1") (pinfunction "DI1_DIN_C1") (pintype "input"))
    )
    (net (code "49") (name "Net-(X14B-DI1-PadDIN_C)") (class "Default")
      (node (ref "X14") (pin "DIN_C") (pinfunction "DI1_DIN_C") (pintype "input"))
      (node (ref "X14") (pin "DIN_C1") (pinfunction "DI1_DIN_C1") (pintype "input"))
      (node (ref "X8") (pin "2-DOUT") (pinfunction "DO_2-DOUT") (pintype "output"))
      (node (ref "X8") (pin "DOUT") (pinfunction "DO_DOUT") (pintype "output"))
      (node (ref "X8") (pin "DOUT1") (pinfunction "DO_DOUT1") (pintype "output"))
      (node (ref "X9") (pin "4-DIN") (pinfunction "DI_4-DIN") (pintype "input"))
      (node (ref "X9") (pin "DIN") (pinfunction "DI_DIN") (pintype "input"))
      (node (ref "X9") (pin "DIN1") (pinfunction "DI_DIN1") (pintype "input"))
    )
    (net (code "50") (name "Net-(X15-PadDA)") (class "Default")
      (node (ref "X15") (pin "D+") (pinfunction "DA_D+") (pintype "bidirectional"))
      (node (ref "X15") (pin "DA") (pinfunction "DA_DA") (pintype "bidirectional"))
    )
    (net (code "51") (name "Net-(X15B-DI-Pad4-DIN)") (class "Default")
      (node (ref "X15") (pin "4-DIN") (pinfunction "DI_4-DIN") (pintype "input"))
      (node (ref "X15") (pin "DIN") (pinfunction "DI_DIN") (pintype "input"))
      (node (ref "X15") (pin "DIN1") (pinfunction "DI_DIN1") (pintype "input"))
      (node (ref "X16") (pin "2-DOUT") (pinfunction "DO_2-DOUT") (pintype "output"))
      (node (ref "X16") (pin "DOUT") (pinfunction "DO_DOUT") (pintype "output"))
      (node (ref "X16") (pin "DOUT1") (pinfunction "DO_DOUT1") (pintype "output"))
      (node (ref "X22") (pin "DIN_C") (pinfunction "DI1_DIN_C") (pintype "input"))
      (node (ref "X22") (pin "DIN_C1") (pinfunction "DI1_DIN_C1") (pintype "input"))
    )
    (net (code "52") (name "Net-(X16-PadDA)") (class "Default")
      (node (ref "X16") (pin "D+") (pinfunction "DA_D+") (pintype "bidirectional"))
      (node (ref "X16") (pin "DA") (pinfunction "DA_DA") (pintype "bidirectional"))
    )
    (net (code "53") (name "Net-(X16B-DI-Pad4-DIN)") (class "Default")
      (node (ref "X16") (pin "4-DIN") (pinfunction "DI_4-DIN") (pintype "input"))
      (node (ref "X16") (pin "DIN") (pinfunction "DI_DIN") (pintype "input"))
      (node (ref "X16") (pin "DIN1") (pinfunction "DI_DIN1") (pintype "input"))
      (node (ref "X17") (pin "2-DOUT") (pinfunction "DO_2-DOUT") (pintype "output"))
      (node (ref "X17") (pin "DOUT") (pinfunction "DO_DOUT") (pintype "output"))
      (node (ref "X17") (pin "DOUT1") (pinfunction "DO_DOUT1") (pintype "output"))
      (node (ref "X23") (pin "DIN_C") (pinfunction "DI1_DIN_C") (pintype "input"))
      (node (ref "X23") (pin "DIN_C1") (pinfunction "DI1_DIN_C1") (pintype "input"))
    )
    (net (code "54") (name "Net-(X17-PadDA)") (class "Default")
      (node (ref "X17") (pin "D+") (pinfunction "DA_D+") (pintype "bidirectional"))
      (node (ref "X17") (pin "DA") (pinfunction "DA_DA") (pintype "bidirectional"))
    )
    (net (code "55") (name "Net-(X17B-DI-Pad4-DIN)") (class "Default")
      (node (ref "X17") (pin "4-DIN") (pinfunction "DI_4-DIN") (pintype "input"))
      (node (ref "X17") (pin "DIN") (pinfunction "DI_DIN") (pintype "input"))
      (node (ref "X17") (pin "DIN1") (pinfunction "DI_DIN1") (pintype "input"))
      (node (ref "X18") (pin "2-DOUT") (pinfunction "DO_2-DOUT") (pintype "output"))
      (node (ref "X18") (pin "DOUT") (pinfunction "DO_DOUT") (pintype "output"))
      (node (ref "X18") (pin "DOUT1") (pinfunction "DO_DOUT1") (pintype "output"))
      (node (ref "X24") (pin "DIN_C") (pinfunction "DI1_DIN_C") (pintype "input"))
      (node (ref "X24") (pin "DIN_C1") (pinfunction "DI1_DIN_C1") (pintype "input"))
    )
    (net (code "56") (name "Net-(X18-PadDA)") (class "Default")
      (node (ref "X18") (pin "D+") (pinfunction "DA_D+") (pintype "bidirectional"))
      (node (ref "X18") (pin "DA") (pinfunction "DA_DA") (pintype "bidirectional"))
    )
    (net (code "57") (name "Net-(X18B-DI-Pad4-DIN)") (class "Default")
      (node (ref "X18") (pin "4-DIN") (pinfunction "DI_4-DIN") (pintype "input"))
      (node (ref "X18") (pin "DIN") (pinfunction "DI_DIN") (pintype "input"))
      (node (ref "X18") (pin "DIN1") (pinfunction "DI_DIN1") (pintype "input"))
    )
    (net (code "58") (name "Net-(X19-PadDA)") (class "Default")
      (node (ref "X19") (pin "D+") (pinfunction "DA_D+") (pintype "bidirectional"))
      (node (ref "X19") (pin "DA") (pinfunction "DA_DA") (pintype "bidirectional"))
    )
    (net (code "59") (name "Net-(X19B-DI-Pad4-DIN)") (class "Default")
      (node (ref "X19") (pin "4-DIN") (pinfunction "DI_4-DIN") (pintype "input"))
      (node (ref "X19") (pin "DIN") (pinfunction "DI_DIN") (pintype "input"))
      (node (ref "X19") (pin "DIN1") (pinfunction "DI_DIN1") (pintype "input"))
    )
    (net (code "60") (name "Net-(X19B-DO-Pad2-DOUT)") (class "Default")
      (node (ref "X19") (pin "2-DOUT") (pinfunction "DO_2-DOUT") (pintype "output"))
      (node (ref "X19") (pin "DOUT") (pinfunction "DO_DOUT") (pintype "output"))
      (node (ref "X19") (pin "DOUT1") (pinfunction "DO_DOUT1") (pintype "output"))
      (node (ref "X20") (pin "4-DIN") (pinfunction "DI_4-DIN") (pintype "input"))
      (node (ref "X20") (pin "DIN") (pinfunction "DI_DIN") (pintype "input"))
      (node (ref "X20") (pin "DIN1") (pinfunction "DI_DIN1") (pintype "input"))
      (node (ref "X25") (pin "DIN_C") (pinfunction "DI1_DIN_C") (pintype "input"))
      (node (ref "X25") (pin "DIN_C1") (pinfunction "DI1_DIN_C1") (pintype "input"))
    )
    (net (code "61") (name "Net-(X20-PadDA)") (class "Default")
      (node (ref "X20") (pin "D+") (pinfunction "DA_D+") (pintype "bidirectional"))
      (node (ref "X20") (pin "DA") (pinfunction "DA_DA") (pintype "bidirectional"))
    )
    (net (code "62") (name "Net-(X20B-DO-Pad2-DOUT)") (class "Default")
      (node (ref "X20") (pin "2-DOUT") (pinfunction "DO_2-DOUT") (pintype "output"))
      (node (ref "X20") (pin "DOUT") (pinfunction "DO_DOUT") (pintype "output"))
      (node (ref "X20") (pin "DOUT1") (pinfunction "DO_DOUT1") (pintype "output"))
      (node (ref "X21") (pin "4-DIN") (pinfunction "DI_4-DIN") (pintype "input"))
      (node (ref "X21") (pin "DIN") (pinfunction "DI_DIN") (pintype "input"))
      (node (ref "X21") (pin "DIN1") (pinfunction "DI_DIN1") (pintype "input"))
      (node (ref "X26") (pin "DIN_C") (pinfunction "DI1_DIN_C") (pintype "input"))
      (node (ref "X26") (pin "DIN_C1") (pinfunction "DI1_DIN_C1") (pintype "input"))
    )
    (net (code "63") (name "Net-(X21-PadDA)") (class "Default")
      (node (ref "X21") (pin "D+") (pinfunction "DA_D+") (pintype "bidirectional"))
      (node (ref "X21") (pin "DA") (pinfunction "DA_DA") (pintype "bidirectional"))
    )
    (net (code "64") (name "Net-(X21B-DO-Pad2-DOUT)") (class "Default")
      (node (ref "X21") (pin "2-DOUT") (pinfunction "DO_2-DOUT") (pintype "output"))
      (node (ref "X21") (pin "DOUT") (pinfunction "DO_DOUT") (pintype "output"))
      (node (ref "X21") (pin "DOUT1") (pinfunction "DO_DOUT1") (pintype "output"))
      (node (ref "X22") (pin "4-DIN") (pinfunction "DI_4-DIN") (pintype "input"))
      (node (ref "X22") (pin "DIN") (pinfunction "DI_DIN") (pintype "input"))
      (node (ref "X22") (pin "DIN1") (pinfunction "DI_DIN1") (pintype "input"))
      (node (ref "X27") (pin "DIN_C") (pinfunction "DI1_DIN_C") (pintype "input"))
      (node (ref "X27") (pin "DIN_C1") (pinfunction "DI1_DIN_C1") (pintype "input"))
    )
    (net (code "65") (name "Net-(X22-PadDA)") (class "Default")
      (node (ref "X22") (pin "D+") (pinfunction "DA_D+") (pintype "bidirectional"))
      (node (ref "X22") (pin "DA") (pinfunction "DA_DA") (pintype "bidirectional"))
    )
    (net (code "66") (name "Net-(X22B-DO-Pad2-DOUT)") (class "Default")
      (node (ref "X22") (pin "2-DOUT") (pinfunction "DO_2-DOUT") (pintype "output"))
      (node (ref "X22") (pin "DOUT") (pinfunction "DO_DOUT") (pintype "output"))
      (node (ref "X22") (pin "DOUT1") (pinfunction "DO_DOUT1") (pintype "output"))
      (node (ref "X23") (pin "4-DIN") (pinfunction "DI_4-DIN") (pintype "input"))
      (node (ref "X23") (pin "DIN") (pinfunction "DI_DIN") (pintype "input"))
      (node (ref "X23") (pin "DIN1") (pinfunction "DI_DIN1") (pintype "input"))
      (node (ref "X28") (pin "DIN_C") (pinfunction "DI1_DIN_C") (pintype "input"))
      (node (ref "X28") (pin "DIN_C1") (pinfunction "DI1_DIN_C1") (pintype "input"))
    )
    (net (code "67") (name "Net-(X23-PadDA)") (class "Default")
      (node (ref "X23") (pin "D+") (pinfunction "DA_D+") (pintype "bidirectional"))
      (node (ref "X23") (pin "DA") (pinfunction "DA_DA") (pintype "bidirectional"))
    )
    (net (code "68") (name "Net-(X23B-DO-Pad2-DOUT)") (class "Default")
      (node (ref "X23") (pin "2-DOUT") (pinfunction "DO_2-DOUT") (pintype "output"))
      (node (ref "X23") (pin "DOUT") (pinfunction "DO_DOUT") (pintype "output"))
      (node (ref "X23") (pin "DOUT1") (pinfunction "DO_DOUT1") (pintype "output"))
      (node (ref "X24") (pin "4-DIN") (pinfunction "DI_4-DIN") (pintype "input"))
      (node (ref "X24") (pin "DIN") (pinfunction "DI_DIN") (pintype "input"))
      (node (ref "X24") (pin "DIN1") (pinfunction "DI_DIN1") (pintype "input"))
      (node (ref "X29") (pin "DIN_C") (pinfunction "DI1_DIN_C") (pintype "input"))
      (node (ref "X29") (pin "DIN_C1") (pinfunction "DI1_DIN_C1") (pintype "input"))
    )
    (net (code "69") (name "Net-(X24-PadDA)") (class "Default")
      (node (ref "X24") (pin "D+") (pinfunction "DA_D+") (pintype "bidirectional"))
      (node (ref "X24") (pin "DA") (pinfunction "DA_DA") (pintype "bidirectional"))
    )
    (net (code "70") (name "Net-(X24B-DO-Pad2-DOUT)") (class "Default")
      (node (ref "X24") (pin "2-DOUT") (pinfunction "DO_2-DOUT") (pintype "output"))
      (node (ref "X24") (pin "DOUT") (pinfunction "DO_DOUT") (pintype "output"))
      (node (ref "X24") (pin "DOUT1") (pinfunction "DO_DOUT1") (pintype "output"))
      (node (ref "X30") (pin "DIN_C") (pinfunction "DI1_DIN_C") (pintype "input"))
      (node (ref "X30") (pin "DIN_C1") (pinfunction "DI1_DIN_C1") (pintype "input"))
    )
    (net (code "71") (name "Net-(X25-PadDA)") (class "Default")
      (node (ref "X25") (pin "D+") (pinfunction "DA_D+") (pintype "bidirectional"))
      (node (ref "X25") (pin "DA") (pinfunction "DA_DA") (pintype "bidirectional"))
    )
    (net (code "72") (name "Net-(X25B-DI-Pad4-DIN)") (class "Default")
      (node (ref "X25") (pin "4-DIN") (pinfunction "DI_4-DIN") (pintype "input"))
      (node (ref "X25") (pin "DIN") (pinfunction "DI_DIN") (pintype "input"))
      (node (ref "X25") (pin "DIN1") (pinfunction "DI_DIN1") (pintype "input"))
      (node (ref "X26") (pin "2-DOUT") (pinfunction "DO_2-DOUT") (pintype "output"))
      (node (ref "X26") (pin "DOUT") (pinfunction "DO_DOUT") (pintype "output"))
      (node (ref "X26") (pin "DOUT1") (pinfunction "DO_DOUT1") (pintype "output"))
    )
    (net (code "73") (name "Net-(X25B-DO-Pad2-DOUT)") (class "Default")
      (node (ref "X25") (pin "2-DOUT") (pinfunction "DO_2-DOUT") (pintype "output"))
      (node (ref "X25") (pin "DOUT") (pinfunction "DO_DOUT") (pintype "output"))
      (node (ref "X25") (pin "DOUT1") (pinfunction "DO_DOUT1") (pintype "output"))
    )
    (net (code "74") (name "Net-(X26-PadDA)") (class "Default")
      (node (ref "X26") (pin "D+") (pinfunction "DA_D+") (pintype "bidirectional"))
      (node (ref "X26") (pin "DA") (pinfunction "DA_DA") (pintype "bidirectional"))
    )
    (net (code "75") (name "Net-(X26B-DI-Pad4-DIN)") (class "Default")
      (node (ref "X26") (pin "4-DIN") (pinfunction "DI_4-DIN") (pintype "input"))
      (node (ref "X26") (pin "DIN") (pinfunction "DI_DIN") (pintype "input"))
      (node (ref "X26") (pin "DIN1") (pinfunction "DI_DIN1") (pintype "input"))
      (node (ref "X27") (pin "2-DOUT") (pinfunction "DO_2-DOUT") (pintype "output"))
      (node (ref "X27") (pin "DOUT") (pinfunction "DO_DOUT") (pintype "output"))
      (node (ref "X27") (pin "DOUT1") (pinfunction "DO_DOUT1") (pintype "output"))
    )
    (net (code "76") (name "Net-(X27-PadDA)") (class "Default")
      (node (ref "X27") (pin "D+") (pinfunction "DA_D+") (pintype "bidirectional"))
      (node (ref "X27") (pin "DA") (pinfunction "DA_DA") (pintype "bidirectional"))
    )
    (net (code "77") (name "Net-(X27B-DI-Pad4-DIN)") (class "Default")
      (node (ref "X27") (pin "4-DIN") (pinfunction "DI_4-DIN") (pintype "input"))
      (node (ref "X27") (pin "DIN") (pinfunction "DI_DIN") (pintype "input"))
      (node (ref "X27") (pin "DIN1") (pinfunction "DI_DIN1") (pintype "input"))
      (node (ref "X28") (pin "2-DOUT") (pinfunction "DO_2-DOUT") (pintype "output"))
      (node (ref "X28") (pin "DOUT") (pinfunction "DO_DOUT") (pintype "output"))
      (node (ref "X28") (pin "DOUT1") (pinfunction "DO_DOUT1") (pintype "output"))
    )
    (net (code "78") (name "Net-(X28-PadDA)") (class "Default")
      (node (ref "X28") (pin "D+") (pinfunction "DA_D+") (pintype "bidirectional"))
      (node (ref "X28") (pin "DA") (pinfunction "DA_DA") (pintype "bidirectional"))
    )
    (net (code "79") (name "Net-(X28B-DI-Pad4-DIN)") (class "Default")
      (node (ref "X28") (pin "4-DIN") (pinfunction "DI_4-DIN") (pintype "input"))
      (node (ref "X28") (pin "DIN") (pinfunction "DI_DIN") (pintype "input"))
      (node (ref "X28") (pin "DIN1") (pinfunction "DI_DIN1") (pintype "input"))
      (node (ref "X29") (pin "2-DOUT") (pinfunction "DO_2-DOUT") (pintype "output"))
      (node (ref "X29") (pin "DOUT") (pinfunction "DO_DOUT") (pintype "output"))
      (node (ref "X29") (pin "DOUT1") (pinfunction "DO_DOUT1") (pintype "output"))
    )
    (net (code "80") (name "Net-(X29-PadDA)") (class "Default")
      (node (ref "X29") (pin "D+") (pinfunction "DA_D+") (pintype "bidirectional"))
      (node (ref "X29") (pin "DA") (pinfunction "DA_DA") (pintype "bidirectional"))
    )
    (net (code "81") (name "Net-(X29B-DI-Pad4-DIN)") (class "Default")
      (node (ref "X29") (pin "4-DIN") (pinfunction "DI_4-DIN") (pintype "input"))
      (node (ref "X29") (pin "DIN") (pinfunction "DI_DIN") (pintype "input"))
      (node (ref "X29") (pin "DIN1") (pinfunction "DI_DIN1") (pintype "input"))
      (node (ref "X30") (pin "2-DOUT") (pinfunction "DO_2-DOUT") (pintype "output"))
      (node (ref "X30") (pin "DOUT") (pinfunction "DO_DOUT") (pintype "output"))
      (node (ref "X30") (pin "DOUT1") (pinfunction "DO_DOUT1") (pintype "output"))
    )
    (net (code "82") (name "Net-(X30-PadDA)") (class "Default")
      (node (ref "X30") (pin "D+") (pinfunction "DA_D+") (pintype "bidirectional"))
      (node (ref "X30") (pin "DA") (pinfunction "DA_DA") (pintype "bidirectional"))
    )
    (net (code "83") (name "Net-(X30B-DI-Pad4-DIN)") (class "Default")
      (node (ref "X30") (pin "4-DIN") (pinfunction "DI_4-DIN") (pintype "input"))
      (node (ref "X30") (pin "DIN") (pinfunction "DI_DIN") (pintype "input"))
      (node (ref "X30") (pin "DIN1") (pinfunction "DI_DIN1") (pintype "input"))
    )
    (net (code "84") (name "VDD") (class "Default")
      (node (ref "X1") (pin "1-VDD") (pinfunction "VDD_1-VDD") (pintype "power_in"))
      (node (ref "X1") (pin "C+") (pinfunction "VDD_C+") (pintype "power_in"))
      (node (ref "X1") (pin "VDD1") (pinfunction "VDD_VDD1") (pintype "power_in"))
      (node (ref "X1") (pin "VDD2") (pinfunction "VDD_VDD2") (pintype "power_in"))
      (node (ref "X10") (pin "1-VDD") (pinfunction "VDD_1-VDD") (pintype "power_in"))
      (node (ref "X10") (pin "C+") (pinfunction "VDD_C+") (pintype "power_in"))
      (node (ref "X10") (pin "VDD1") (pinfunction "VDD_VDD1") (pintype "power_in"))
      (node (ref "X10") (pin "VDD2") (pinfunction "VDD_VDD2") (pintype "power_in"))
      (node (ref "X11") (pin "1-VDD") (pinfunction "VDD_1-VDD") (pintype "power_in"))
      (node (ref "X11") (pin "C+") (pinfunction "VDD_C+") (pintype "power_in"))
      (node (ref "X11") (pin "VDD1") (pinfunction "VDD_VDD1") (pintype "power_in"))
      (node (ref "X11") (pin "VDD2") (pinfunction "VDD_VDD2") (pintype "power_in"))
      (node (ref "X12") (pin "1-VDD") (pinfunction "VDD_1-VDD") (pintype "power_in"))
      (node (ref "X12") (pin "C+") (pinfunction "VDD_C+") (pintype "power_in"))
      (node (ref "X12") (pin "VDD1") (pinfunction "VDD_VDD1") (pintype "power_in"))
      (node (ref "X12") (pin "VDD2") (pinfunction "VDD_VDD2") (pintype "power_in"))
      (node (ref "X13") (pin "1-VDD") (pinfunction "VDD_1-VDD") (pintype "power_in"))
      (node (ref "X13") (pin "C+") (pinfunction "VDD_C+") (pintype "power_in"))
      (node (ref "X13") (pin "VDD1") (pinfunction "VDD_VDD1") (pintype "power_in"))
      (node (ref "X13") (pin "VDD2") (pinfunction "VDD_VDD2") (pintype "power_in"))
      (node (ref "X14") (pin "1-VDD") (pinfunction "VDD_1-VDD") (pintype "power_in"))
      (node (ref "X14") (pin "C+") (pinfunction "VDD_C+") (pintype "power_in"))
      (node (ref "X14") (pin "VDD1") (pinfunction "VDD_VDD1") (pintype "power_in"))
      (node (ref "X14") (pin "VDD2") (pinfunction "VDD_VDD2") (pintype "power_in"))
      (node (ref "X15") (pin "1-VDD") (pinfunction "VDD_1-VDD") (pintype "power_in"))
      (node (ref "X15") (pin "C+") (pinfunction "VDD_C+") (pintype "power_in"))
      (node (ref "X15") (pin "VDD1") (pinfunction "VDD_VDD1") (pintype "power_in"))
      (node (ref "X15") (pin "VDD2") (pinfunction "VDD_VDD2") (pintype "power_in"))
      (node (ref "X16") (pin "1-VDD") (pinfunction "VDD_1-VDD") (pintype "power_in"))
      (node (ref "X16") (pin "C+") (pinfunction "VDD_C+") (pintype "power_in"))
      (node (ref "X16") (pin "VDD1") (pinfunction "VDD_VDD1") (pintype "power_in"))
      (node (ref "X16") (pin "VDD2") (pinfunction "VDD_VDD2") (pintype "power_in"))
      (node (ref "X17") (pin "1-VDD") (pinfunction "VDD_1-VDD") (pintype "power_in"))
      (node (ref "X17") (pin "C+") (pinfunction "VDD_C+") (pintype "power_in"))
      (node (ref "X17") (pin "VDD1") (pinfunction "VDD_VDD1") (pintype "power_in"))
      (node (ref "X17") (pin "VDD2") (pinfunction "VDD_VDD2") (pintype "power_in"))
      (node (ref "X18") (pin "1-VDD") (pinfunction "VDD_1-VDD") (pintype "power_in"))
      (node (ref "X18") (pin "C+") (pinfunction "VDD_C+") (pintype "power_in"))
      (node (ref "X18") (pin "VDD1") (pinfunction "VDD_VDD1") (pintype "power_in"))
      (node (ref "X18") (pin "VDD2") (pinfunction "VDD_VDD2") (pintype "power_in"))
      (node (ref "X19") (pin "1-VDD") (pinfunction "VDD_1-VDD") (pintype "power_in"))
      (node (ref "X19") (pin "C+") (pinfunction "VDD_C+") (pintype "power_in"))
      (node (ref "X19") (pin "VDD1") (pinfunction "VDD_VDD1") (pintype "power_in"))
      (node (ref "X19") (pin "VDD2") (pinfunction "VDD_VDD2") (pintype "power_in"))
      (node (ref "X2") (pin "1-VDD") (pinfunction "VDD_1-VDD") (pintype "power_in"))
      (node (ref "X2") (pin "C+") (pinfunction "VDD_C+") (pintype "power_in"))
      (node (ref "X2") (pin "VDD1") (pinfunction "VDD_VDD1") (pintype "power_in"))
      (node (ref "X2") (pin "VDD2") (pinfunction "VDD_VDD2") (pintype "power_in"))
      (node (ref "X20") (pin "1-VDD") (pinfunction "VDD_1-VDD") (pintype "power_in"))
      (node (ref "X20") (pin "C+") (pinfunction "VDD_C+") (pintype "power_in"))
      (node (ref "X20") (pin "VDD1") (pinfunction "VDD_VDD1") (pintype "power_in"))
      (node (ref "X20") (pin "VDD2") (pinfunction "VDD_VDD2") (pintype "power_in"))
      (node (ref "X21") (pin "1-VDD") (pinfunction "VDD_1-VDD") (pintype "power_in"))
      (node (ref "X21") (pin "C+") (pinfunction "VDD_C+") (pintype "power_in"))
      (node (ref "X21") (pin "VDD1") (pinfunction "VDD_VDD1") (pintype "power_in"))
      (node (ref "X21") (pin "VDD2") (pinfunction "VDD_VDD2") (pintype "power_in"))
      (node (ref "X22") (pin "1-VDD") (pinfunction "VDD_1-VDD") (pintype "power_in"))
      (node (ref "X22") (pin "C+") (pinfunction "VDD_C+") (pintype "power_in"))
      (node (ref "X22") (pin "VDD1") (pinfunction "VDD_VDD1") (pintype "power_in"))
      (node (ref "X22") (pin "VDD2") (pinfunction "VDD_VDD2") (pintype "power_in"))
      (node (ref "X23") (pin "1-VDD") (pinfunction "VDD_1-VDD") (pintype "power_in"))
      (node (ref "X23") (pin "C+") (pinfunction "VDD_C+") (pintype "power_in"))
      (node (ref "X23") (pin "VDD1") (pinfunction "VDD_VDD1") (pintype "power_in"))
      (node (ref "X23") (pin "VDD2") (pinfunction "VDD_VDD2") (pintype "power_in"))
      (node (ref "X24") (pin "1-VDD") (pinfunction "VDD_1-VDD") (pintype "power_in"))
      (node (ref "X24") (pin "C+") (pinfunction "VDD_C+") (pintype "power_in"))
      (node (ref "X24") (pin "VDD1") (pinfunction "VDD_VDD1") (pintype "power_in"))
      (node (ref "X24") (pin "VDD2") (pinfunction "VDD_VDD2") (pintype "power_in"))
      (node (ref "X25") (pin "1-VDD") (pinfunction "VDD_1-VDD") (pintype "power_in"))
      (node (ref "X25") (pin "C+") (pinfunction "VDD_C+") (pintype "power_in"))
      (node (ref "X25") (pin "VDD1") (pinfunction "VDD_VDD1") (pintype "power_in"))
      (node (ref "X25") (pin "VDD2") (pinfunction "VDD_VDD2") (pintype "power_in"))
      (node (ref "X26") (pin "1-VDD") (pinfunction "VDD_1-VDD") (pintype "power_in"))
      (node (ref "X26") (pin "C+") (pinfunction "VDD_C+") (pintype "power_in"))
      (node (ref "X26") (pin "VDD1") (pinfunction "VDD_VDD1") (pintype "power_in"))
      (node (ref "X26") (pin "VDD2") (pinfunction "VDD_VDD2") (pintype "power_in"))
      (node (ref "X27") (pin "1-VDD") (pinfunction "VDD_1-VDD") (pintype "power_in"))
      (node (ref "X27") (pin "C+") (pinfunction "VDD_C+") (pintype "power_in"))
      (node (ref "X27") (pin "VDD1") (pinfunction "VDD_VDD1") (pintype "power_in"))
      (node (ref "X27") (pin "VDD2") (pinfunction "VDD_VDD2") (pintype "power_in"))
      (node (ref "X28") (pin "1-VDD") (pinfunction "VDD_1-VDD") (pintype "power_in"))
      (node (ref "X28") (pin "C+") (pinfunction "VDD_C+") (pintype "power_in"))
      (node (ref "X28") (pin "VDD1") (pinfunction "VDD_VDD1") (pintype "power_in"))
      (node (ref "X28") (pin "VDD2") (pinfunction "VDD_VDD2") (pintype "power_in"))
      (node (ref "X29") (pin "1-VDD") (pinfunction "VDD_1-VDD") (pintype "power_in"))
      (node (ref "X29") (pin "C+") (pinfunction "VDD_C+") (pintype "power_in"))
      (node (ref "X29") (pin "VDD1") (pinfunction "VDD_VDD1") (pintype "power_in"))
      (node (ref "X29") (pin "VDD2") (pinfunction "VDD_VDD2") (pintype "power_in"))
      (node (ref "X3") (pin "1-VDD") (pinfunction "VDD_1-VDD") (pintype "power_in"))
      (node (ref "X3") (pin "C+") (pinfunction "VDD_C+") (pintype "power_in"))
      (node (ref "X3") (pin "VDD1") (pinfunction "VDD_VDD1") (pintype "power_in"))
      (node (ref "X3") (pin "VDD2") (pinfunction "VDD_VDD2") (pintype "power_in"))
      (node (ref "X30") (pin "1-VDD") (pinfunction "VDD_1-VDD") (pintype "power_in"))
      (node (ref "X30") (pin "C+") (pinfunction "VDD_C+") (pintype "power_in"))
      (node (ref "X30") (pin "VDD1") (pinfunction "VDD_VDD1") (pintype "power_in"))
      (node (ref "X30") (pin "VDD2") (pinfunction "VDD_VDD2") (pintype "power_in"))
      (node (ref "X4") (pin "1-VDD") (pinfunction "VDD_1-VDD") (pintype "power_in"))
      (node (ref "X4") (pin "C+") (pinfunction "VDD_C+") (pintype "power_in"))
      (node (ref "X4") (pin "VDD1") (pinfunction "VDD_VDD1") (pintype "power_in"))
      (node (ref "X4") (pin "VDD2") (pinfunction "VDD_VDD2") (pintype "power_in"))
      (node (ref "X5") (pin "1-VDD") (pinfunction "VDD_1-VDD") (pintype "power_in"))
      (node (ref "X5") (pin "C+") (pinfunction "VDD_C+") (pintype "power_in"))
      (node (ref "X5") (pin "VDD1") (pinfunction "VDD_VDD1") (pintype "power_in"))
      (node (ref "X5") (pin "VDD2") (pinfunction "VDD_VDD2") (pintype "power_in"))
      (node (ref "X6") (pin "1-VDD") (pinfunction "VDD_1-VDD") (pintype "power_in"))
      (node (ref "X6") (pin "C+") (pinfunction "VDD_C+") (pintype "power_in"))
      (node (ref "X6") (pin "VDD1") (pinfunction "VDD_VDD1") (pintype "power_in"))
      (node (ref "X6") (pin "VDD2") (pinfunction "VDD_VDD2") (pintype "power_in"))
      (node (ref "X7") (pin "1-VDD") (pinfunction "VDD_1-VDD") (pintype "power_in"))
      (node (ref "X7") (pin "C+") (pinfunction "VDD_C+") (pintype "power_in"))
      (node (ref "X7") (pin "VDD1") (pinfunction "VDD_VDD1") (pintype "power_in"))
      (node (ref "X7") (pin "VDD2") (pinfunction "VDD_VDD2") (pintype "power_in"))
      (node (ref "X8") (pin "1-VDD") (pinfunction "VDD_1-VDD") (pintype "power_in"))
      (node (ref "X8") (pin "C+") (pinfunction "VDD_C+") (pintype "power_in"))
      (node (ref "X8") (pin "VDD1") (pinfunction "VDD_VDD1") (pintype "power_in"))
      (node (ref "X8") (pin "VDD2") (pinfunction "VDD_VDD2") (pintype "power_in"))
      (node (ref "X9") (pin "1-VDD") (pinfunction "VDD_1-VDD") (pintype "power_in"))
      (node (ref "X9") (pin "C+") (pinfunction "VDD_C+") (pintype "power_in"))
      (node (ref "X9") (pin "VDD1") (pinfunction "VDD_VDD1") (pintype "power_in"))
      (node (ref "X9") (pin "VDD2") (pinfunction "VDD_VDD2") (pintype "power_in"))
    )
  )
)
